# FFPTD.net
KiCad netlist of a schematic drawn in EAGLE
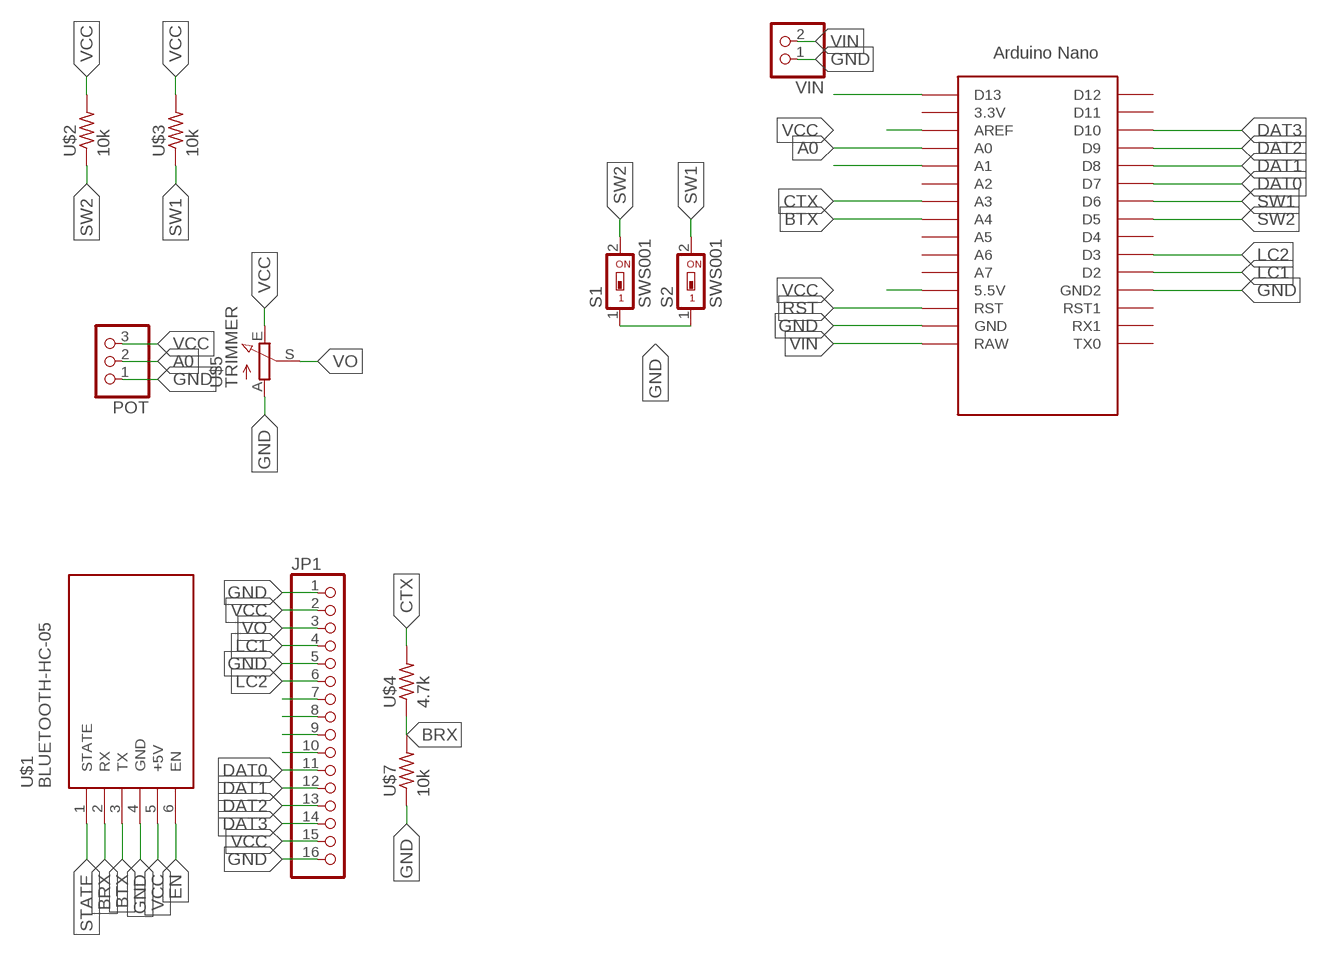
[diagram p0: schematic, sheet 1]

(export (version "E")
  (design (tool "Eeschema 10.0.6"))
  (components
    (comp (ref "JP1")
      (value "PINHD-1X16")
      (footprint "eagle-import:1X16")
      (libsource (lib "eagle-import") (part "PINHD-1X16"))
    )
    (comp (ref "POT")
      (value "PINHD-1X3")
      (footprint "eagle-import:1X03")
      (libsource (lib "eagle-import") (part "PINHD-1X3"))
    )
    (comp (ref "S1")
      (value "SWS001")
      (footprint "eagle-import:SMS-001")
      (libsource (lib "eagle-import") (part "SWS001"))
    )
    (comp (ref "S2")
      (value "SWS001")
      (footprint "eagle-import:SMS-001")
      (libsource (lib "eagle-import") (part "SWS001"))
    )
    (comp (ref "U$1")
      (value "BLUETOOTH-HC-05")
      (footprint "eagle-import:WIRELESS-BLUETOOTH-HC-05")
      (libsource (lib "eagle-import") (part "BLUETOOTH-HC-05"))
    )
    (comp (ref "U$2")
      (value "10k")
      (footprint "eagle-import:0204_7")
      (libsource (lib "eagle-import") (part "RES-7"))
    )
    (comp (ref "U$3")
      (value "10k")
      (footprint "eagle-import:0204_7")
      (libsource (lib "eagle-import") (part "RES-7"))
    )
    (comp (ref "U$4")
      (value "4.7k")
      (footprint "eagle-import:0204_7")
      (libsource (lib "eagle-import") (part "RES-7"))
    )
    (comp (ref "U$5")
      (value "TRIMMER")
      (footprint "eagle-import:RJ9W")
      (libsource (lib "eagle-import") (part "TRIMMER"))
    )
    (comp (ref "U$6")
      (value "ARDUINO_NANO")
      (footprint "eagle-import:NANO")
      (libsource (lib "eagle-import") (part "ARDUINO_NANO"))
    )
    (comp (ref "U$7")
      (value "10k")
      (footprint "eagle-import:0204_7")
      (libsource (lib "eagle-import") (part "RES-7"))
    )
    (comp (ref "VIN")
      (value "PINHD-1X2")
      (footprint "eagle-import:1X02")
      (libsource (lib "eagle-import") (part "PINHD-1X2"))
    )
  )
  (nets
    (net (code "1") (name "A0") (class "Default")
      (node (ref "POT") (pin "2") (pinfunction "2_2") (pintype "passive"))
      (node (ref "U$6") (pin "A0") (pinfunction "A0_A0") (pintype "bidirectional"))
    )
    (net (code "2") (name "BRX") (class "Default")
      (node (ref "U$1") (pin "2") (pinfunction "RX_2") (pintype "bidirectional"))
      (node (ref "U$4") (pin "1") (pinfunction "1_1") (pintype "passive"))
      (node (ref "U$7") (pin "2") (pinfunction "2_2") (pintype "passive"))
    )
    (net (code "3") (name "BTX") (class "Default")
      (node (ref "U$1") (pin "3") (pinfunction "TX_3") (pintype "bidirectional"))
      (node (ref "U$6") (pin "A4") (pinfunction "A4_A4") (pintype "bidirectional"))
    )
    (net (code "4") (name "CTX") (class "Default")
      (node (ref "U$4") (pin "2") (pinfunction "2_2") (pintype "passive"))
      (node (ref "U$6") (pin "A3") (pinfunction "A3_A3") (pintype "bidirectional"))
    )
    (net (code "5") (name "DAT0") (class "Default")
      (node (ref "JP1") (pin "11") (pinfunction "11_11") (pintype "passive"))
      (node (ref "U$6") (pin "D7") (pinfunction "D7_D7") (pintype "bidirectional"))
    )
    (net (code "6") (name "DAT1") (class "Default")
      (node (ref "JP1") (pin "12") (pinfunction "12_12") (pintype "passive"))
      (node (ref "U$6") (pin "D8") (pinfunction "D8_D8") (pintype "bidirectional"))
    )
    (net (code "7") (name "DAT2") (class "Default")
      (node (ref "JP1") (pin "13") (pinfunction "13_13") (pintype "passive"))
      (node (ref "U$6") (pin "D9") (pinfunction "D9_D9") (pintype "bidirectional"))
    )
    (net (code "8") (name "DAT3") (class "Default")
      (node (ref "JP1") (pin "14") (pinfunction "14_14") (pintype "passive"))
      (node (ref "U$6") (pin "D10") (pinfunction "D10_D10") (pintype "bidirectional"))
    )
    (net (code "9") (name "EN") (class "Default")
      (node (ref "U$1") (pin "6") (pinfunction "EN_6") (pintype "bidirectional"))
    )
    (net (code "10") (name "GND") (class "Default")
      (node (ref "JP1") (pin "1") (pinfunction "1_1") (pintype "passive"))
      (node (ref "JP1") (pin "16") (pinfunction "16_16") (pintype "passive"))
      (node (ref "JP1") (pin "5") (pinfunction "5_5") (pintype "passive"))
      (node (ref "POT") (pin "1") (pinfunction "1_1") (pintype "passive"))
      (node (ref "S1") (pin "1") (pinfunction "1_1") (pintype "passive"))
      (node (ref "S2") (pin "1") (pinfunction "1_1") (pintype "passive"))
      (node (ref "U$1") (pin "4") (pinfunction "GND_4") (pintype "power_in"))
      (node (ref "U$5") (pin "A") (pinfunction "A_A") (pintype "passive"))
      (node (ref "U$6") (pin "GND") (pinfunction "GND_GND") (pintype "bidirectional"))
      (node (ref "U$6") (pin "GND1") (pinfunction "GND2_GND1") (pintype "bidirectional"))
      (node (ref "U$7") (pin "1") (pinfunction "1_1") (pintype "passive"))
      (node (ref "VIN") (pin "1") (pinfunction "1_1") (pintype "passive"))
    )
    (net (code "11") (name "LC1") (class "Default")
      (node (ref "JP1") (pin "4") (pinfunction "4_4") (pintype "passive"))
      (node (ref "U$6") (pin "D2") (pinfunction "D2_D2") (pintype "bidirectional"))
    )
    (net (code "12") (name "LC2") (class "Default")
      (node (ref "JP1") (pin "6") (pinfunction "6_6") (pintype "passive"))
      (node (ref "U$6") (pin "D3") (pinfunction "D3_D3") (pintype "bidirectional"))
    )
    (net (code "13") (name "RST") (class "Default")
      (node (ref "U$6") (pin "RST") (pinfunction "RST_RST") (pintype "bidirectional"))
    )
    (net (code "14") (name "STATE") (class "Default")
      (node (ref "U$1") (pin "1") (pinfunction "STATE_1") (pintype "bidirectional"))
    )
    (net (code "15") (name "SW1") (class "Default")
      (node (ref "S2") (pin "2") (pinfunction "2_2") (pintype "passive"))
      (node (ref "U$3") (pin "1") (pinfunction "1_1") (pintype "passive"))
      (node (ref "U$6") (pin "D6") (pinfunction "D6_D6") (pintype "bidirectional"))
    )
    (net (code "16") (name "SW2") (class "Default")
      (node (ref "S1") (pin "2") (pinfunction "2_2") (pintype "passive"))
      (node (ref "U$2") (pin "1") (pinfunction "1_1") (pintype "passive"))
      (node (ref "U$6") (pin "D5") (pinfunction "D5_D5") (pintype "bidirectional"))
    )
    (net (code "17") (name "VCC") (class "Default")
      (node (ref "JP1") (pin "15") (pinfunction "15_15") (pintype "passive"))
      (node (ref "JP1") (pin "2") (pinfunction "2_2") (pintype "passive"))
      (node (ref "POT") (pin "3") (pinfunction "3_3") (pintype "passive"))
      (node (ref "U$1") (pin "5") (pinfunction "+5V_5") (pintype "power_in"))
      (node (ref "U$2") (pin "2") (pinfunction "2_2") (pintype "passive"))
      (node (ref "U$3") (pin "2") (pinfunction "2_2") (pintype "passive"))
      (node (ref "U$5") (pin "E") (pinfunction "E_E") (pintype "passive"))
      (node (ref "U$6") (pin "5V") (pinfunction "5.5V_5V") (pintype "bidirectional"))
      (node (ref "U$6") (pin "AREF") (pinfunction "AREF_AREF") (pintype "bidirectional"))
    )
    (net (code "18") (name "VIN") (class "Default")
      (node (ref "U$6") (pin "RAW") (pinfunction "RAW_RAW") (pintype "bidirectional"))
      (node (ref "VIN") (pin "2") (pinfunction "2_2") (pintype "passive"))
    )
    (net (code "19") (name "VO") (class "Default")
      (node (ref "JP1") (pin "3") (pinfunction "3_3") (pintype "passive"))
      (node (ref "U$5") (pin "S") (pinfunction "S_S") (pintype "passive"))
    )
    (net (code "20") (name "unconnected-(JP1-Pad7)") (class "Default")
      (node (ref "JP1") (pin "7") (pinfunction "7_7") (pintype "passive"))
    )
    (net (code "21") (name "unconnected-(JP1-Pad8)") (class "Default")
      (node (ref "JP1") (pin "8") (pinfunction "8_8") (pintype "passive"))
    )
    (net (code "22") (name "unconnected-(JP1-Pad9)") (class "Default")
      (node (ref "JP1") (pin "9") (pinfunction "9_9") (pintype "passive"))
    )
    (net (code "23") (name "unconnected-(JP1-Pad10)") (class "Default")
      (node (ref "JP1") (pin "10") (pinfunction "10_10") (pintype "passive"))
    )
    (net (code "24") (name "unconnected-(U$6-Pad3.3V)") (class "Default")
      (node (ref "U$6") (pin "3.3V") (pinfunction "3.3V_3.3V") (pintype "bidirectional"))
    )
    (net (code "25") (name "unconnected-(U$6-PadA1)") (class "Default")
      (node (ref "U$6") (pin "A1") (pinfunction "A1_A1") (pintype "bidirectional"))
    )
    (net (code "26") (name "unconnected-(U$6-PadA2)") (class "Default")
      (node (ref "U$6") (pin "A2") (pinfunction "A2_A2") (pintype "bidirectional"))
    )
    (net (code "27") (name "unconnected-(U$6-PadA5)") (class "Default")
      (node (ref "U$6") (pin "A5") (pinfunction "A5_A5") (pintype "bidirectional"))
    )
    (net (code "28") (name "unconnected-(U$6-PadA6)") (class "Default")
      (node (ref "U$6") (pin "A6") (pinfunction "A6_A6") (pintype "bidirectional"))
    )
    (net (code "29") (name "unconnected-(U$6-PadA7)") (class "Default")
      (node (ref "U$6") (pin "A7") (pinfunction "A7_A7") (pintype "bidirectional"))
    )
    (net (code "30") (name "unconnected-(U$6-PadD4)") (class "Default")
      (node (ref "U$6") (pin "D4") (pinfunction "D4_D4") (pintype "bidirectional"))
    )
    (net (code "31") (name "unconnected-(U$6-PadD11)") (class "Default")
      (node (ref "U$6") (pin "D11") (pinfunction "D11_D11") (pintype "bidirectional"))
    )
    (net (code "32") (name "unconnected-(U$6-PadD12)") (class "Default")
      (node (ref "U$6") (pin "D12") (pinfunction "D12_D12") (pintype "bidirectional"))
    )
    (net (code "33") (name "unconnected-(U$6-PadD13)") (class "Default")
      (node (ref "U$6") (pin "D13") (pinfunction "D13_D13") (pintype "bidirectional"))
    )
    (net (code "34") (name "unconnected-(U$6-PadRST1)") (class "Default")
      (node (ref "U$6") (pin "RST1") (pinfunction "RST1_RST1") (pintype "bidirectional"))
    )
    (net (code "35") (name "unconnected-(U$6-PadRX1)") (class "Default")
      (node (ref "U$6") (pin "RX1") (pinfunction "RX1_RX1") (pintype "bidirectional"))
    )
    (net (code "36") (name "unconnected-(U$6-PadTX0)") (class "Default")
      (node (ref "U$6") (pin "TX0") (pinfunction "TX0_TX0") (pintype "bidirectional"))
    )
  )
)
